# DicioWRK.net
KiCad netlist of a schematic drawn in EAGLE
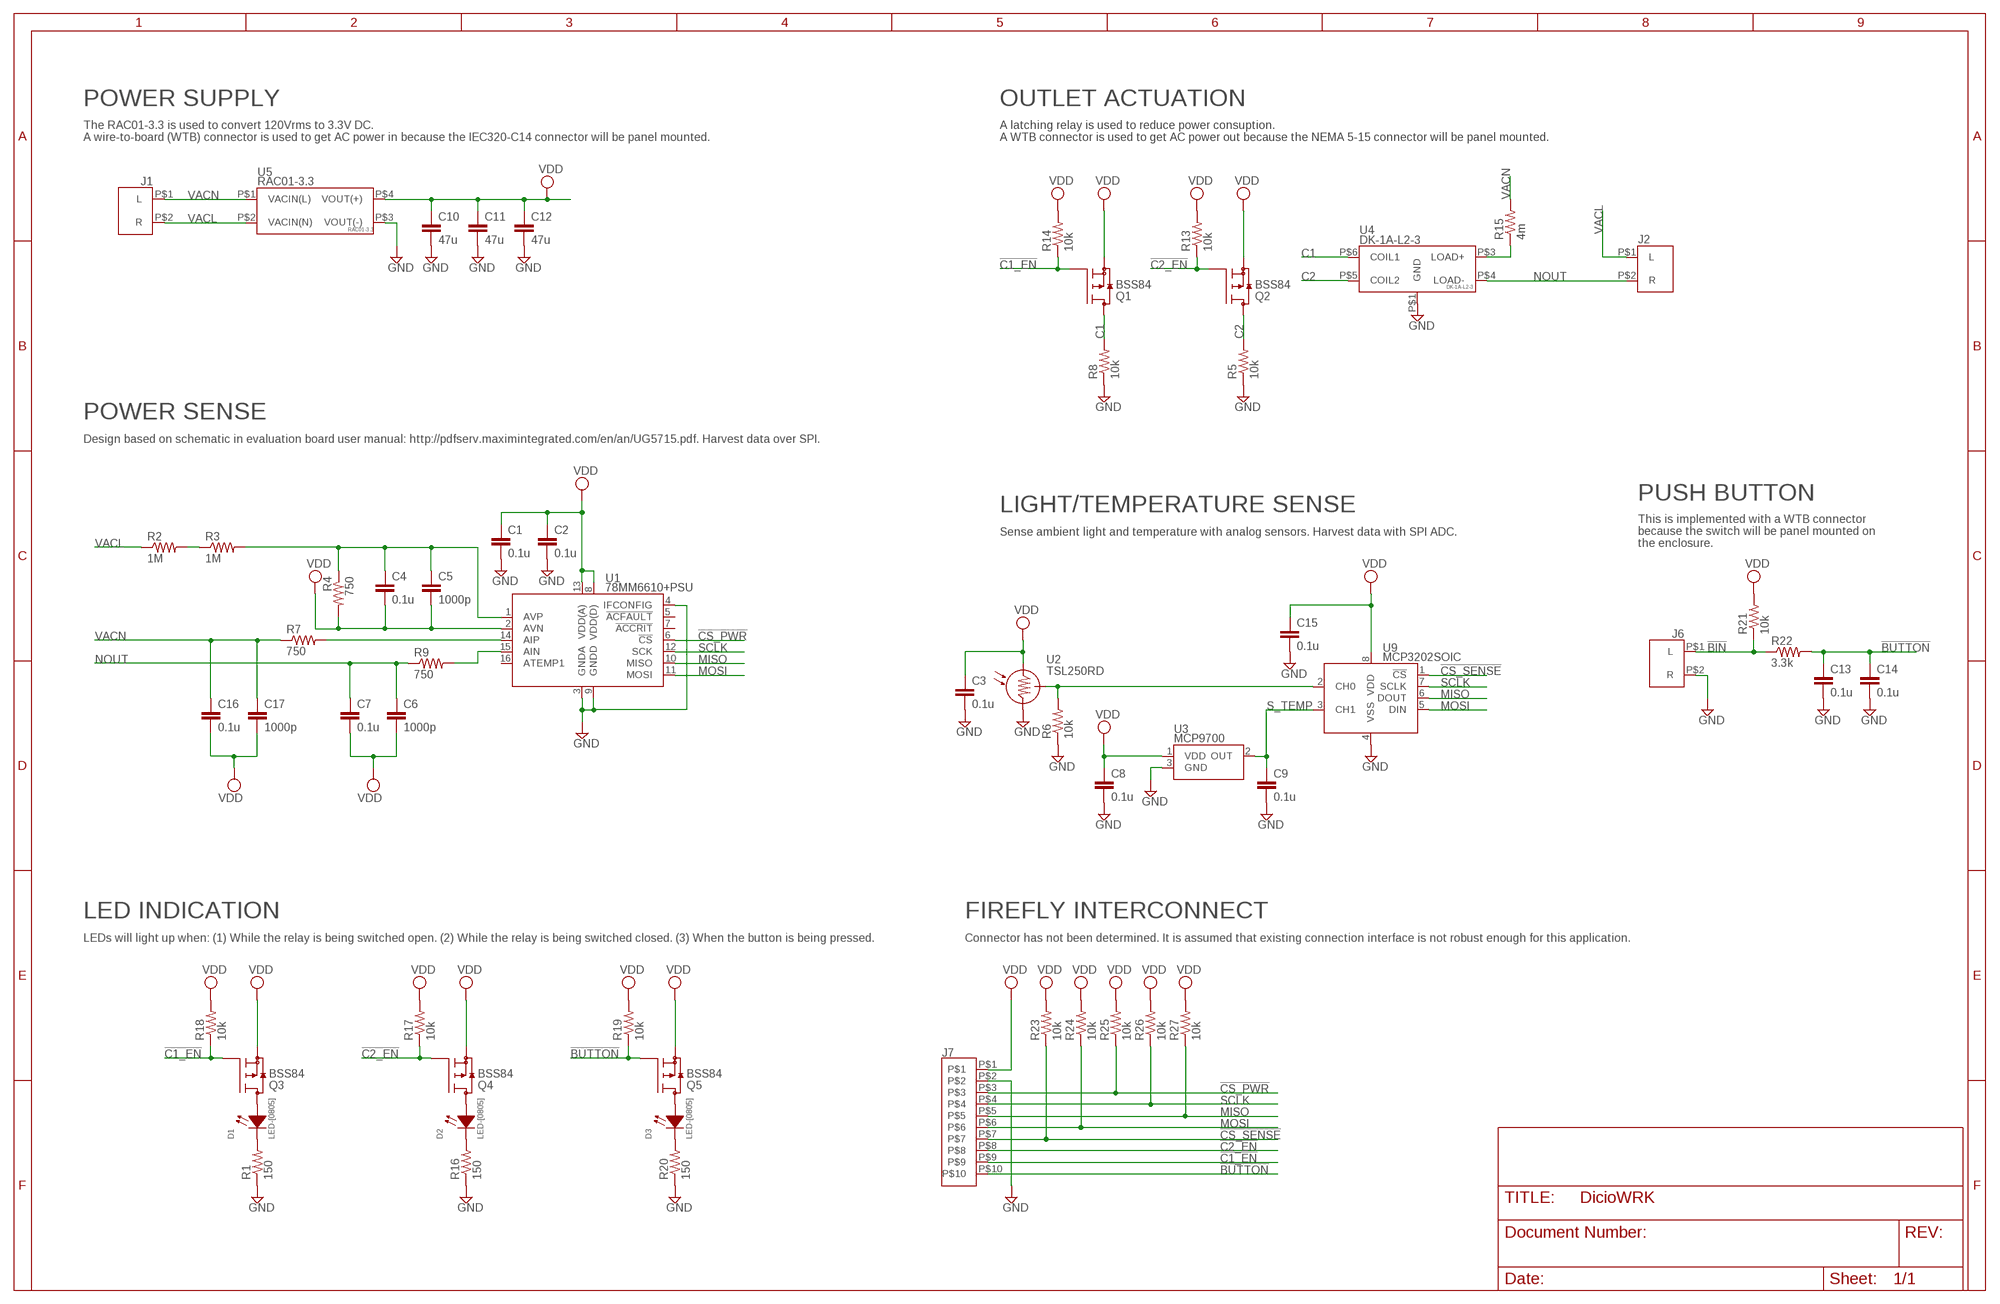
[diagram p0: schematic, sheet 1]

(export (version "E")
  (design (tool "Eeschema 10.0.6"))
  (components
    (comp (ref "C1")
      (value "0.1u")
      (footprint "eagle-import:C0805")
      (libsource (lib "eagle-import") (part "C-EUC0805"))
    )
    (comp (ref "C2")
      (value "0.1u")
      (footprint "eagle-import:C0805")
      (libsource (lib "eagle-import") (part "C-EUC0805"))
    )
    (comp (ref "C3")
      (value "0.1u")
      (footprint "eagle-import:C0805")
      (libsource (lib "eagle-import") (part "C-EUC0805"))
    )
    (comp (ref "C4")
      (value "0.1u")
      (footprint "eagle-import:C0805")
      (libsource (lib "eagle-import") (part "C-EUC0805"))
    )
    (comp (ref "C5")
      (value "1000p")
      (footprint "eagle-import:C0805")
      (libsource (lib "eagle-import") (part "C-EUC0805"))
    )
    (comp (ref "C6")
      (value "1000p")
      (footprint "eagle-import:C0805")
      (libsource (lib "eagle-import") (part "C-EUC0805"))
    )
    (comp (ref "C7")
      (value "0.1u")
      (footprint "eagle-import:C0805")
      (libsource (lib "eagle-import") (part "C-EUC0805"))
    )
    (comp (ref "C8")
      (value "0.1u")
      (footprint "eagle-import:C0805")
      (libsource (lib "eagle-import") (part "C-EUC0805"))
    )
    (comp (ref "C9")
      (value "0.1u")
      (footprint "eagle-import:C0805")
      (libsource (lib "eagle-import") (part "C-EUC0805"))
    )
    (comp (ref "C10")
      (value "47u")
      (footprint "eagle-import:C1206")
      (libsource (lib "eagle-import") (part "C-EUC1206"))
    )
    (comp (ref "C11")
      (value "47u")
      (footprint "eagle-import:C1206")
      (libsource (lib "eagle-import") (part "C-EUC1206"))
    )
    (comp (ref "C12")
      (value "47u")
      (footprint "eagle-import:C1206")
      (libsource (lib "eagle-import") (part "C-EUC1206"))
    )
    (comp (ref "C13")
      (value "0.1u")
      (footprint "eagle-import:C0805")
      (libsource (lib "eagle-import") (part "C-EUC0805"))
    )
    (comp (ref "C14")
      (value "0.1u")
      (footprint "eagle-import:C0805")
      (libsource (lib "eagle-import") (part "C-EUC0805"))
    )
    (comp (ref "C15")
      (value "0.1u")
      (footprint "eagle-import:C0805")
      (libsource (lib "eagle-import") (part "C-EUC0805"))
    )
    (comp (ref "C16")
      (value "0.1u")
      (footprint "eagle-import:C0805")
      (libsource (lib "eagle-import") (part "C-EUC0805"))
    )
    (comp (ref "C17")
      (value "1000p")
      (footprint "eagle-import:C0805")
      (libsource (lib "eagle-import") (part "C-EUC0805"))
    )
    (comp (ref "D1")
      (value "LED-[0805]")
      (footprint "eagle-import:L0805")
      (libsource (lib "eagle-import") (part "LED-[0805]"))
    )
    (comp (ref "D2")
      (value "LED-[0805]")
      (footprint "eagle-import:L0805")
      (libsource (lib "eagle-import") (part "LED-[0805]"))
    )
    (comp (ref "D3")
      (value "LED-[0805]")
      (footprint "eagle-import:L0805")
      (libsource (lib "eagle-import") (part "LED-[0805]"))
    )
    (comp (ref "J1")
      (value "WTB-2")
      (footprint "eagle-import:[TERM][2][0.2]")
      (libsource (lib "eagle-import") (part "WTB-2"))
    )
    (comp (ref "J2")
      (value "WTB-2")
      (footprint "eagle-import:[TERM][2][0.2]")
      (libsource (lib "eagle-import") (part "WTB-2"))
    )
    (comp (ref "J6")
      (value "WTB-2")
      (footprint "eagle-import:[TERM][2][0.2]")
      (libsource (lib "eagle-import") (part "WTB-2"))
    )
    (comp (ref "J7")
      (value "TERM10")
      (footprint "eagle-import:TERM10")
      (libsource (lib "eagle-import") (part "TERM10"))
    )
    (comp (ref "Q1")
      (value "BSS84")
      (footprint "eagle-import:SOT23")
      (libsource (lib "eagle-import") (part "BSS84"))
    )
    (comp (ref "Q2")
      (value "BSS84")
      (footprint "eagle-import:SOT23")
      (libsource (lib "eagle-import") (part "BSS84"))
    )
    (comp (ref "Q3")
      (value "BSS84")
      (footprint "eagle-import:SOT23")
      (libsource (lib "eagle-import") (part "BSS84"))
    )
    (comp (ref "Q4")
      (value "BSS84")
      (footprint "eagle-import:SOT23")
      (libsource (lib "eagle-import") (part "BSS84"))
    )
    (comp (ref "Q5")
      (value "BSS84")
      (footprint "eagle-import:SOT23")
      (libsource (lib "eagle-import") (part "BSS84"))
    )
    (comp (ref "R1")
      (value "150")
      (footprint "eagle-import:R0805")
      (libsource (lib "eagle-import") (part "R-US_R0805"))
    )
    (comp (ref "R2")
      (value "1M")
      (footprint "eagle-import:R0805")
      (libsource (lib "eagle-import") (part "R-US_R0805"))
    )
    (comp (ref "R3")
      (value "1M")
      (footprint "eagle-import:R0805")
      (libsource (lib "eagle-import") (part "R-US_R0805"))
    )
    (comp (ref "R4")
      (value "750")
      (footprint "eagle-import:R0805")
      (libsource (lib "eagle-import") (part "R-US_R0805"))
    )
    (comp (ref "R5")
      (value "10k")
      (footprint "eagle-import:R0805")
      (libsource (lib "eagle-import") (part "R-US_R0805"))
    )
    (comp (ref "R6")
      (value "10k")
      (footprint "eagle-import:R0805")
      (libsource (lib "eagle-import") (part "R-US_R0805"))
    )
    (comp (ref "R7")
      (value "750")
      (footprint "eagle-import:R0805")
      (libsource (lib "eagle-import") (part "R-US_R0805"))
    )
    (comp (ref "R8")
      (value "10k")
      (footprint "eagle-import:R0805")
      (libsource (lib "eagle-import") (part "R-US_R0805"))
    )
    (comp (ref "R9")
      (value "750")
      (footprint "eagle-import:R0805")
      (libsource (lib "eagle-import") (part "R-US_R0805"))
    )
    (comp (ref "R13")
      (value "10k")
      (footprint "eagle-import:R0805")
      (libsource (lib "eagle-import") (part "R-US_R0805"))
    )
    (comp (ref "R14")
      (value "10k")
      (footprint "eagle-import:R0805")
      (libsource (lib "eagle-import") (part "R-US_R0805"))
    )
    (comp (ref "R15")
      (value "4m")
      (footprint "eagle-import:R2512")
      (libsource (lib "eagle-import") (part "R-US_R2512"))
    )
    (comp (ref "R16")
      (value "150")
      (footprint "eagle-import:R0805")
      (libsource (lib "eagle-import") (part "R-US_R0805"))
    )
    (comp (ref "R17")
      (value "10k")
      (footprint "eagle-import:R0805")
      (libsource (lib "eagle-import") (part "R-US_R0805"))
    )
    (comp (ref "R18")
      (value "10k")
      (footprint "eagle-import:R0805")
      (libsource (lib "eagle-import") (part "R-US_R0805"))
    )
    (comp (ref "R19")
      (value "10k")
      (footprint "eagle-import:R0805")
      (libsource (lib "eagle-import") (part "R-US_R0805"))
    )
    (comp (ref "R20")
      (value "150")
      (footprint "eagle-import:R0805")
      (libsource (lib "eagle-import") (part "R-US_R0805"))
    )
    (comp (ref "R21")
      (value "10k")
      (footprint "eagle-import:R0805")
      (libsource (lib "eagle-import") (part "R-US_R0805"))
    )
    (comp (ref "R22")
      (value "3.3k")
      (footprint "eagle-import:R0805")
      (libsource (lib "eagle-import") (part "R-US_R0805"))
    )
    (comp (ref "R23")
      (value "10k")
      (footprint "eagle-import:R0805")
      (libsource (lib "eagle-import") (part "R-US_R0805"))
    )
    (comp (ref "R24")
      (value "10k")
      (footprint "eagle-import:R0805")
      (libsource (lib "eagle-import") (part "R-US_R0805"))
    )
    (comp (ref "R25")
      (value "10k")
      (footprint "eagle-import:R0805")
      (libsource (lib "eagle-import") (part "R-US_R0805"))
    )
    (comp (ref "R26")
      (value "10k")
      (footprint "eagle-import:R0805")
      (libsource (lib "eagle-import") (part "R-US_R0805"))
    )
    (comp (ref "R27")
      (value "10k")
      (footprint "eagle-import:R0805")
      (libsource (lib "eagle-import") (part "R-US_R0805"))
    )
    (comp (ref "U1")
      (value "78MM6610+PSU")
      (footprint "eagle-import:TSSOP16")
      (libsource (lib "eagle-import") (part "78MM6610+PSU"))
    )
    (comp (ref "U2")
      (value "TSL250RD")
      (footprint "eagle-import:SOIC8")
      (libsource (lib "eagle-import") (part "TSL250RD"))
    )
    (comp (ref "U3")
      (value "MCP9700")
      (footprint "eagle-import:SOT23")
      (libsource (lib "eagle-import") (part "MCP9700"))
    )
    (comp (ref "U4")
      (value "DK-1A-L2-3")
      (footprint "eagle-import:DK-1A-L2-3")
      (libsource (lib "eagle-import") (part "DK-1A-L2-3"))
    )
    (comp (ref "U5")
      (value "RAC01-3.3")
      (footprint "eagle-import:RAC01-3.3")
      (libsource (lib "eagle-import") (part "RAC01-3.3"))
    )
    (comp (ref "U9")
      (value "MCP3202SOIC")
      (footprint "eagle-import:SOIC8")
      (libsource (lib "eagle-import") (part "MCP3202SOIC"))
    )
  )
  (nets
    (net (code "1") (name "/C1") (class "Default")
      (node (ref "Q1") (pin "3") (pinfunction "D_3") (pintype "bidirectional"))
      (node (ref "R8") (pin "2") (pinfunction "2_2") (pintype "passive"))
      (node (ref "U4") (pin "P$6") (pinfunction "COIL1_P$6") (pintype "bidirectional"))
    )
    (net (code "2") (name "/C2") (class "Default")
      (node (ref "Q2") (pin "3") (pinfunction "D_3") (pintype "bidirectional"))
      (node (ref "R5") (pin "2") (pinfunction "2_2") (pintype "passive"))
      (node (ref "U4") (pin "P$5") (pinfunction "COIL2_P$5") (pintype "bidirectional"))
    )
    (net (code "3") (name "/MISO") (class "Default")
      (node (ref "J7") (pin "P$5") (pinfunction "P$5_P$5") (pintype "bidirectional"))
      (node (ref "R27") (pin "1") (pinfunction "1_1") (pintype "passive"))
      (node (ref "U1") (pin "10") (pinfunction "MISO_10") (pintype "bidirectional"))
      (node (ref "U9") (pin "6") (pinfunction "DOUT_6") (pintype "bidirectional"))
    )
    (net (code "4") (name "/MOSI") (class "Default")
      (node (ref "J7") (pin "P$6") (pinfunction "P$6_P$6") (pintype "bidirectional"))
      (node (ref "R24") (pin "1") (pinfunction "1_1") (pintype "passive"))
      (node (ref "U1") (pin "11") (pinfunction "MOSI_11") (pintype "bidirectional"))
      (node (ref "U9") (pin "5") (pinfunction "DIN_5") (pintype "bidirectional"))
    )
    (net (code "5") (name "/NOUT") (class "Default")
      (node (ref "C6") (pin "1") (pinfunction "1_1") (pintype "passive"))
      (node (ref "C7") (pin "1") (pinfunction "1_1") (pintype "passive"))
      (node (ref "J2") (pin "P$2") (pinfunction "R_P$2") (pintype "bidirectional"))
      (node (ref "R9") (pin "1") (pinfunction "1_1") (pintype "passive"))
      (node (ref "U4") (pin "P$4") (pinfunction "LOAD-_P$4") (pintype "bidirectional"))
    )
    (net (code "6") (name "/SCLK") (class "Default")
      (node (ref "J7") (pin "P$4") (pinfunction "P$4_P$4") (pintype "bidirectional"))
      (node (ref "R26") (pin "1") (pinfunction "1_1") (pintype "passive"))
      (node (ref "U1") (pin "12") (pinfunction "SCK_12") (pintype "bidirectional"))
      (node (ref "U9") (pin "7") (pinfunction "SCLK_7") (pintype "bidirectional"))
    )
    (net (code "7") (name "/S_TEMP") (class "Default")
      (node (ref "C9") (pin "1") (pinfunction "1_1") (pintype "passive"))
      (node (ref "U3") (pin "2") (pinfunction "OUT_2") (pintype "bidirectional"))
      (node (ref "U9") (pin "3") (pinfunction "CH1_3") (pintype "bidirectional"))
    )
    (net (code "8") (name "/VACL") (class "Default")
      (node (ref "J1") (pin "P$2") (pinfunction "R_P$2") (pintype "bidirectional"))
      (node (ref "J2") (pin "P$1") (pinfunction "L_P$1") (pintype "bidirectional"))
      (node (ref "R2") (pin "1") (pinfunction "1_1") (pintype "passive"))
      (node (ref "U5") (pin "P$2") (pinfunction "VACIN(N)_P$2") (pintype "bidirectional"))
    )
    (net (code "9") (name "/VACN") (class "Default")
      (node (ref "C16") (pin "1") (pinfunction "1_1") (pintype "passive"))
      (node (ref "C17") (pin "1") (pinfunction "1_1") (pintype "passive"))
      (node (ref "J1") (pin "P$1") (pinfunction "L_P$1") (pintype "bidirectional"))
      (node (ref "R15") (pin "2") (pinfunction "2_2") (pintype "passive"))
      (node (ref "R7") (pin "1") (pinfunction "1_1") (pintype "passive"))
      (node (ref "U5") (pin "P$1") (pinfunction "VACIN(L)_P$1") (pintype "bidirectional"))
    )
    (net (code "10") (name "/~{BIN}") (class "Default")
      (node (ref "J6") (pin "P$1") (pinfunction "L_P$1") (pintype "bidirectional"))
      (node (ref "R21") (pin "1") (pinfunction "1_1") (pintype "passive"))
      (node (ref "R22") (pin "1") (pinfunction "1_1") (pintype "passive"))
    )
    (net (code "11") (name "/~{BUTTON}") (class "Default")
      (node (ref "C13") (pin "1") (pinfunction "1_1") (pintype "passive"))
      (node (ref "C14") (pin "1") (pinfunction "1_1") (pintype "passive"))
      (node (ref "J7") (pin "P$10") (pinfunction "P$10_P$10") (pintype "bidirectional"))
      (node (ref "Q5") (pin "1") (pinfunction "G_1") (pintype "bidirectional"))
      (node (ref "R19") (pin "1") (pinfunction "1_1") (pintype "passive"))
      (node (ref "R22") (pin "2") (pinfunction "2_2") (pintype "passive"))
    )
    (net (code "12") (name "/~{C1_EN}") (class "Default")
      (node (ref "J7") (pin "P$9") (pinfunction "P$9_P$9") (pintype "bidirectional"))
      (node (ref "Q1") (pin "1") (pinfunction "G_1") (pintype "bidirectional"))
      (node (ref "Q3") (pin "1") (pinfunction "G_1") (pintype "bidirectional"))
      (node (ref "R14") (pin "1") (pinfunction "1_1") (pintype "passive"))
      (node (ref "R18") (pin "1") (pinfunction "1_1") (pintype "passive"))
    )
    (net (code "13") (name "/~{C2_EN}") (class "Default")
      (node (ref "J7") (pin "P$8") (pinfunction "P$8_P$8") (pintype "bidirectional"))
      (node (ref "Q2") (pin "1") (pinfunction "G_1") (pintype "bidirectional"))
      (node (ref "Q4") (pin "1") (pinfunction "G_1") (pintype "bidirectional"))
      (node (ref "R13") (pin "1") (pinfunction "1_1") (pintype "passive"))
      (node (ref "R17") (pin "1") (pinfunction "1_1") (pintype "passive"))
    )
    (net (code "14") (name "/~{CS_PWR}") (class "Default")
      (node (ref "J7") (pin "P$3") (pinfunction "P$3_P$3") (pintype "bidirectional"))
      (node (ref "R25") (pin "1") (pinfunction "1_1") (pintype "passive"))
      (node (ref "U1") (pin "6") (pinfunction "~{CS}_6") (pintype "bidirectional"))
    )
    (net (code "15") (name "/~{CS_SENSE}") (class "Default")
      (node (ref "J7") (pin "P$7") (pinfunction "P$7_P$7") (pintype "bidirectional"))
      (node (ref "R23") (pin "1") (pinfunction "1_1") (pintype "passive"))
      (node (ref "U9") (pin "1") (pinfunction "~{CS}_1") (pintype "bidirectional"))
    )
    (net (code "16") (name "GND") (class "Default")
      (node (ref "C1") (pin "2") (pinfunction "2_2") (pintype "passive"))
      (node (ref "C10") (pin "2") (pinfunction "2_2") (pintype "passive"))
      (node (ref "C11") (pin "2") (pinfunction "2_2") (pintype "passive"))
      (node (ref "C12") (pin "2") (pinfunction "2_2") (pintype "passive"))
      (node (ref "C13") (pin "2") (pinfunction "2_2") (pintype "passive"))
      (node (ref "C14") (pin "2") (pinfunction "2_2") (pintype "passive"))
      (node (ref "C15") (pin "2") (pinfunction "2_2") (pintype "passive"))
      (node (ref "C2") (pin "2") (pinfunction "2_2") (pintype "passive"))
      (node (ref "C3") (pin "2") (pinfunction "2_2") (pintype "passive"))
      (node (ref "C8") (pin "2") (pinfunction "2_2") (pintype "passive"))
      (node (ref "C9") (pin "2") (pinfunction "2_2") (pintype "passive"))
      (node (ref "J6") (pin "P$2") (pinfunction "R_P$2") (pintype "bidirectional"))
      (node (ref "J7") (pin "P$2") (pinfunction "P$2_P$2") (pintype "bidirectional"))
      (node (ref "R1") (pin "1") (pinfunction "1_1") (pintype "passive"))
      (node (ref "R16") (pin "1") (pinfunction "1_1") (pintype "passive"))
      (node (ref "R20") (pin "1") (pinfunction "1_1") (pintype "passive"))
      (node (ref "R5") (pin "1") (pinfunction "1_1") (pintype "passive"))
      (node (ref "R6") (pin "1") (pinfunction "1_1") (pintype "passive"))
      (node (ref "R8") (pin "1") (pinfunction "1_1") (pintype "passive"))
      (node (ref "U1") (pin "3") (pinfunction "GNDA_3") (pintype "bidirectional"))
      (node (ref "U1") (pin "4") (pinfunction "IFCONFIG_4") (pintype "bidirectional"))
      (node (ref "U1") (pin "9") (pinfunction "GNDD_9") (pintype "bidirectional"))
      (node (ref "U2") (pin "4") (pinfunction "GND_4") (pintype "bidirectional"))
      (node (ref "U3") (pin "3") (pinfunction "GND_3") (pintype "bidirectional"))
      (node (ref "U4") (pin "P$1") (pinfunction "GND_P$1") (pintype "bidirectional"))
      (node (ref "U5") (pin "P$3") (pinfunction "VOUT(-)_P$3") (pintype "bidirectional"))
      (node (ref "U9") (pin "4") (pinfunction "VSS_4") (pintype "bidirectional"))
    )
    (net (code "17") (name "Net-(D1-A)") (class "Default")
      (node (ref "D1") (pin "1") (pinfunction "A_1") (pintype "bidirectional"))
      (node (ref "Q3") (pin "3") (pinfunction "D_3") (pintype "bidirectional"))
    )
    (net (code "18") (name "Net-(D1-C)") (class "Default")
      (node (ref "D1") (pin "2") (pinfunction "C_2") (pintype "bidirectional"))
      (node (ref "R1") (pin "2") (pinfunction "2_2") (pintype "passive"))
    )
    (net (code "19") (name "Net-(D2-A)") (class "Default")
      (node (ref "D2") (pin "1") (pinfunction "A_1") (pintype "bidirectional"))
      (node (ref "Q4") (pin "3") (pinfunction "D_3") (pintype "bidirectional"))
    )
    (net (code "20") (name "Net-(D2-C)") (class "Default")
      (node (ref "D2") (pin "2") (pinfunction "C_2") (pintype "bidirectional"))
      (node (ref "R16") (pin "2") (pinfunction "2_2") (pintype "passive"))
    )
    (net (code "21") (name "Net-(D3-A)") (class "Default")
      (node (ref "D3") (pin "1") (pinfunction "A_1") (pintype "bidirectional"))
      (node (ref "Q5") (pin "3") (pinfunction "D_3") (pintype "bidirectional"))
    )
    (net (code "22") (name "Net-(D3-C)") (class "Default")
      (node (ref "D3") (pin "2") (pinfunction "C_2") (pintype "bidirectional"))
      (node (ref "R20") (pin "2") (pinfunction "2_2") (pintype "passive"))
    )
    (net (code "23") (name "Net-(R2-Pad2)") (class "Default")
      (node (ref "R2") (pin "2") (pinfunction "2_2") (pintype "passive"))
      (node (ref "R3") (pin "1") (pinfunction "1_1") (pintype "passive"))
    )
    (net (code "24") (name "Net-(U1-AIN)") (class "Default")
      (node (ref "R9") (pin "2") (pinfunction "2_2") (pintype "passive"))
      (node (ref "U1") (pin "15") (pinfunction "AIN_15") (pintype "bidirectional"))
    )
    (net (code "25") (name "Net-(U1-AIP)") (class "Default")
      (node (ref "R7") (pin "2") (pinfunction "2_2") (pintype "passive"))
      (node (ref "U1") (pin "14") (pinfunction "AIP_14") (pintype "bidirectional"))
    )
    (net (code "26") (name "Net-(U1-AVP)") (class "Default")
      (node (ref "C4") (pin "1") (pinfunction "1_1") (pintype "passive"))
      (node (ref "C5") (pin "1") (pinfunction "1_1") (pintype "passive"))
      (node (ref "R3") (pin "2") (pinfunction "2_2") (pintype "passive"))
      (node (ref "R4") (pin "1") (pinfunction "1_1") (pintype "passive"))
      (node (ref "U1") (pin "1") (pinfunction "AVP_1") (pintype "bidirectional"))
    )
    (net (code "27") (name "Net-(U2-OUT)") (class "Default")
      (node (ref "R6") (pin "2") (pinfunction "2_2") (pintype "passive"))
      (node (ref "U2") (pin "7") (pinfunction "OUT_7") (pintype "bidirectional"))
      (node (ref "U9") (pin "2") (pinfunction "CH0_2") (pintype "bidirectional"))
    )
    (net (code "28") (name "Net-(U4-LOAD+)") (class "Default")
      (node (ref "R15") (pin "1") (pinfunction "1_1") (pintype "passive"))
      (node (ref "U4") (pin "P$3") (pinfunction "LOAD+_P$3") (pintype "bidirectional"))
    )
    (net (code "29") (name "VDD") (class "Default")
      (node (ref "C1") (pin "1") (pinfunction "1_1") (pintype "passive"))
      (node (ref "C10") (pin "1") (pinfunction "1_1") (pintype "passive"))
      (node (ref "C11") (pin "1") (pinfunction "1_1") (pintype "passive"))
      (node (ref "C12") (pin "1") (pinfunction "1_1") (pintype "passive"))
      (node (ref "C15") (pin "1") (pinfunction "1_1") (pintype "passive"))
      (node (ref "C16") (pin "2") (pinfunction "2_2") (pintype "passive"))
      (node (ref "C17") (pin "2") (pinfunction "2_2") (pintype "passive"))
      (node (ref "C2") (pin "1") (pinfunction "1_1") (pintype "passive"))
      (node (ref "C3") (pin "1") (pinfunction "1_1") (pintype "passive"))
      (node (ref "C4") (pin "2") (pinfunction "2_2") (pintype "passive"))
      (node (ref "C5") (pin "2") (pinfunction "2_2") (pintype "passive"))
      (node (ref "C6") (pin "2") (pinfunction "2_2") (pintype "passive"))
      (node (ref "C7") (pin "2") (pinfunction "2_2") (pintype "passive"))
      (node (ref "C8") (pin "1") (pinfunction "1_1") (pintype "passive"))
      (node (ref "J7") (pin "P$1") (pinfunction "P$1_P$1") (pintype "bidirectional"))
      (node (ref "Q1") (pin "2") (pinfunction "S_2") (pintype "bidirectional"))
      (node (ref "Q2") (pin "2") (pinfunction "S_2") (pintype "bidirectional"))
      (node (ref "Q3") (pin "2") (pinfunction "S_2") (pintype "bidirectional"))
      (node (ref "Q4") (pin "2") (pinfunction "S_2") (pintype "bidirectional"))
      (node (ref "Q5") (pin "2") (pinfunction "S_2") (pintype "bidirectional"))
      (node (ref "R13") (pin "2") (pinfunction "2_2") (pintype "passive"))
      (node (ref "R14") (pin "2") (pinfunction "2_2") (pintype "passive"))
      (node (ref "R17") (pin "2") (pinfunction "2_2") (pintype "passive"))
      (node (ref "R18") (pin "2") (pinfunction "2_2") (pintype "passive"))
      (node (ref "R19") (pin "2") (pinfunction "2_2") (pintype "passive"))
      (node (ref "R21") (pin "2") (pinfunction "2_2") (pintype "passive"))
      (node (ref "R23") (pin "2") (pinfunction "2_2") (pintype "passive"))
      (node (ref "R24") (pin "2") (pinfunction "2_2") (pintype "passive"))
      (node (ref "R25") (pin "2") (pinfunction "2_2") (pintype "passive"))
      (node (ref "R26") (pin "2") (pinfunction "2_2") (pintype "passive"))
      (node (ref "R27") (pin "2") (pinfunction "2_2") (pintype "passive"))
      (node (ref "R4") (pin "2") (pinfunction "2_2") (pintype "passive"))
      (node (ref "U1") (pin "13") (pinfunction "VDD(A)_13") (pintype "bidirectional"))
      (node (ref "U1") (pin "2") (pinfunction "AVN_2") (pintype "bidirectional"))
      (node (ref "U1") (pin "8") (pinfunction "VDD(D)_8") (pintype "bidirectional"))
      (node (ref "U2") (pin "6") (pinfunction "VDD_6") (pintype "bidirectional"))
      (node (ref "U3") (pin "1") (pinfunction "VDD_1") (pintype "bidirectional"))
      (node (ref "U5") (pin "P$4") (pinfunction "VOUT(+)_P$4") (pintype "bidirectional"))
      (node (ref "U9") (pin "8") (pinfunction "VDD_8") (pintype "bidirectional"))
    )
    (net (code "30") (name "unconnected-(U1-ATEMP1-Pad16)") (class "Default")
      (node (ref "U1") (pin "16") (pinfunction "ATEMP1_16") (pintype "bidirectional"))
    )
    (net (code "31") (name "unconnected-(U1-~{ACCRIT}-Pad7)") (class "Default")
      (node (ref "U1") (pin "7") (pinfunction "~{ACCRIT}_7") (pintype "bidirectional"))
    )
    (net (code "32") (name "unconnected-(U1-~{ACFAULT}-Pad5)") (class "Default")
      (node (ref "U1") (pin "5") (pinfunction "~{ACFAULT}_5") (pintype "bidirectional"))
    )
  )
)
